# 3_Channel_Buck_Converter_Schematic.net
KiCad netlist of a schematic drawn in Altium Designer
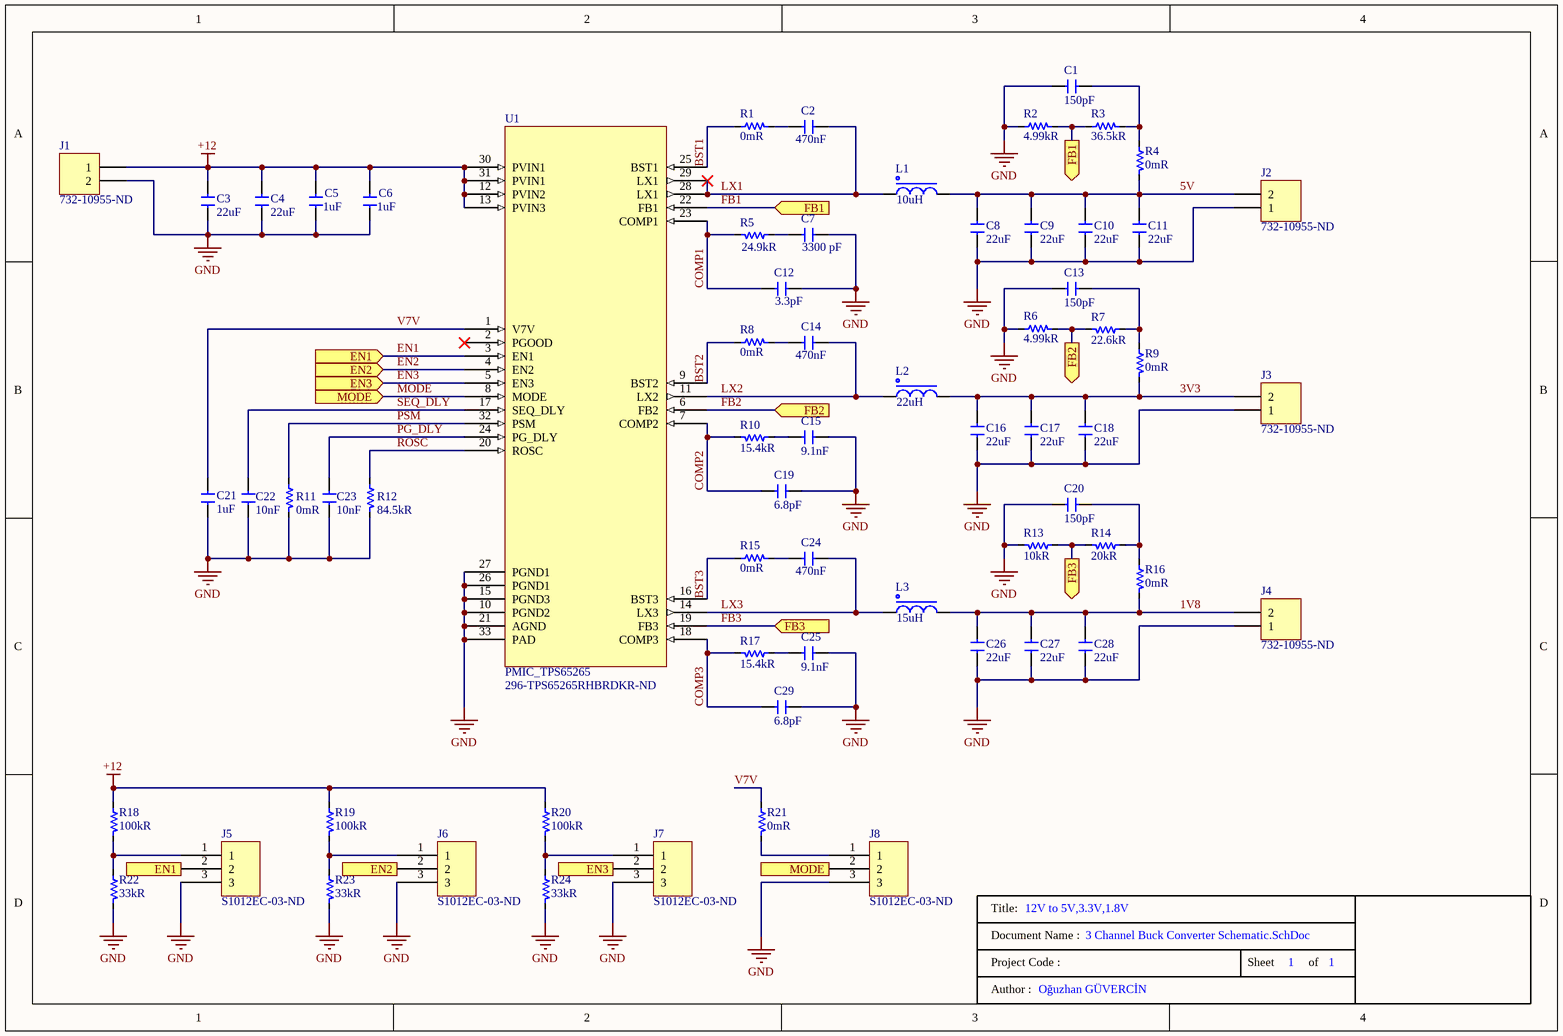
[diagram p0: 3 Channel Buck Converter Schematic.SchDoc]

(export (version "E")
  (design (tool "Eeschema 10.0.6"))
  (components
    (comp (ref "C1")
      (value "CAP_150pF_%1_0603_50V_NP0_CER")
      (footprint "0603_CAP")
      (description "0603 150 pF 50 V ±1 % Tolerance C0G/NP0 SMT Multilayer Ceramic Capacitor")
      (fields
        (field (name "MANUFACTURER") "Kyocera AVX")
        (field (name "MANUFACTURER PART NUMBER") "06035A151FAT2A")
        (field (name "CAPACITANCE") "150pF")
      )
      (libsource (lib "Main Schematic Library") (part "CAP_150pF_%1_0603_50V_NP0_CER"))
    )
    (comp (ref "C2")
      (value "CAP_0.47uF_%10_0603_25V_X7R_CER")
      (footprint "0603_CAP")
      (description "470nF Multilayer Ceramic Capacitor MLCC25 V; X7R Dielectric 0603 Surface Mount")
      (fields
        (field (name "MANUFACTURER") "Wurth Electronics")
        (field (name "MANUFACTURER PART NUMBER") "885012206075")
        (field (name "CAPACITANCE") "470nF")
      )
      (libsource (lib "Main Schematic Library") (part "CAP_0.47uF_%10_0603_25V_X7R_CER"))
    )
    (comp (ref "C3")
      (value "CAP_22uF_%10_1206_25V_X5R_CER")
      (footprint "1206_CAP")
      (description "1206 22 uF 25 V ±10% Tolerance X5R Multilayer Ceramic Chip Capacitor")
      (fields
        (field (name "MANUFACTURER") "Yageo")
        (field (name "MANUFACTURER PART NUMBER") "CC1206KKX5R8BB226")
        (field (name "CAPACITANCE") "22uF")
      )
      (libsource (lib "Main Schematic Library") (part "CAP_22uF_%10_1206_25V_X5R_CER"))
    )
    (comp (ref "C4")
      (value "CAP_22uF_%10_1206_25V_X5R_CER")
      (footprint "1206_CAP")
      (description "1206 22 uF 25 V ±10% Tolerance X5R Multilayer Ceramic Chip Capacitor")
      (fields
        (field (name "MANUFACTURER") "Yageo")
        (field (name "MANUFACTURER PART NUMBER") "CC1206KKX5R8BB226")
        (field (name "CAPACITANCE") "22uF")
      )
      (libsource (lib "Main Schematic Library") (part "CAP_22uF_%10_1206_25V_X5R_CER"))
    )
    (comp (ref "C5")
      (value "CAP_1uF_%10_0603_25V_X7R_CER")
      (footprint "0603_CAP")
      (description "TAPE DUCT CLOTH GRAY 3/4X 50YDS")
      (fields
        (field (name "MANUFACTURER") "Yageo")
        (field (name "MANUFACTURER PART NUMBER") "CC0603KPX7R8BB105")
        (field (name "CAPACITANCE") "1uF")
      )
      (libsource (lib "Main Schematic Library") (part "CAP_1uF_%10_0603_25V_X7R_CER"))
    )
    (comp (ref "C6")
      (value "CAP_1uF_%10_0603_25V_X7R_CER")
      (footprint "0603_CAP")
      (description "TAPE DUCT CLOTH GRAY 3/4X 50YDS")
      (fields
        (field (name "MANUFACTURER") "Yageo")
        (field (name "MANUFACTURER PART NUMBER") "CC0603KPX7R8BB105")
        (field (name "CAPACITANCE") "1uF")
      )
      (libsource (lib "Main Schematic Library") (part "CAP_1uF_%10_0603_25V_X7R_CER"))
    )
    (comp (ref "C7")
      (value "CAP_3300pF_0603_50V_X7R_CER")
      (footprint "0603_CAP")
      (description "3300 pF ±10% 50V Ceramic Capacitor X7R 0603 (1608 Metric)")
      (fields
        (field (name "MANUFACTURER") "Meritek")
        (field (name "MANUFACTURER PART NUMBER") "MA0603XR332K500")
        (field (name "CAPACITANCE") "3300 pF")
      )
      (libsource (lib "Main Schematic Library") (part "CAP_3300pF_0603_50V_X7R_CER"))
    )
    (comp (ref "C8")
      (value "CAP_22uF_%10_1206_25V_X5R_CER")
      (footprint "1206_CAP")
      (description "1206 22 uF 25 V ±10% Tolerance X5R Multilayer Ceramic Chip Capacitor")
      (fields
        (field (name "MANUFACTURER") "Yageo")
        (field (name "MANUFACTURER PART NUMBER") "CC1206KKX5R8BB226")
        (field (name "CAPACITANCE") "22uF")
      )
      (libsource (lib "Main Schematic Library") (part "CAP_22uF_%10_1206_25V_X5R_CER"))
    )
    (comp (ref "C9")
      (value "CAP_22uF_%10_1206_25V_X5R_CER")
      (footprint "1206_CAP")
      (description "1206 22 uF 25 V ±10% Tolerance X5R Multilayer Ceramic Chip Capacitor")
      (fields
        (field (name "MANUFACTURER") "Yageo")
        (field (name "MANUFACTURER PART NUMBER") "CC1206KKX5R8BB226")
        (field (name "CAPACITANCE") "22uF")
      )
      (libsource (lib "Main Schematic Library") (part "CAP_22uF_%10_1206_25V_X5R_CER"))
    )
    (comp (ref "C10")
      (value "CAP_22uF_%10_1206_25V_X5R_CER")
      (footprint "1206_CAP")
      (description "1206 22 uF 25 V ±10% Tolerance X5R Multilayer Ceramic Chip Capacitor")
      (fields
        (field (name "MANUFACTURER") "Yageo")
        (field (name "MANUFACTURER PART NUMBER") "CC1206KKX5R8BB226")
        (field (name "CAPACITANCE") "22uF")
      )
      (libsource (lib "Main Schematic Library") (part "CAP_22uF_%10_1206_25V_X5R_CER"))
    )
    (comp (ref "C11")
      (value "CAP_22uF_%10_1206_25V_X5R_CER")
      (footprint "1206_CAP")
      (description "1206 22 uF 25 V ±10% Tolerance X5R Multilayer Ceramic Chip Capacitor")
      (fields
        (field (name "MANUFACTURER") "Yageo")
        (field (name "MANUFACTURER PART NUMBER") "CC1206KKX5R8BB226")
        (field (name "CAPACITANCE") "22uF")
      )
      (libsource (lib "Main Schematic Library") (part "CAP_22uF_%10_1206_25V_X5R_CER"))
    )
    (comp (ref "C12")
      (value "CAP_3.3pF_±0.1pF_0603_50V_NP0_CER")
      (footprint "0603_CAP")
      (description "0603 3.3 pF 50 V ±0.1 pF Tolerance C0G/NP0 SMT Multilayer Ceramic Capacitor")
      (fields
        (field (name "MANUFACTURER") "Kyocera AVX")
        (field (name "MANUFACTURER PART NUMBER") "06035A3R3BAT2A")
        (field (name "CAPACITANCE") "3.3pF")
      )
      (libsource (lib "Main Schematic Library") (part "CAP_3.3pF_±0.1pF_0603_50V_NP0_CER"))
    )
    (comp (ref "C13")
      (value "CAP_150pF_%1_0603_50V_NP0_CER")
      (footprint "0603_CAP")
      (description "0603 150 pF 50 V ±1 % Tolerance C0G/NP0 SMT Multilayer Ceramic Capacitor")
      (fields
        (field (name "MANUFACTURER") "Kyocera AVX")
        (field (name "MANUFACTURER PART NUMBER") "06035A151FAT2A")
        (field (name "CAPACITANCE") "150pF")
      )
      (libsource (lib "Main Schematic Library") (part "CAP_150pF_%1_0603_50V_NP0_CER"))
    )
    (comp (ref "C14")
      (value "CAP_0.47uF_%10_0603_25V_X7R_CER")
      (footprint "0603_CAP")
      (description "470nF Multilayer Ceramic Capacitor MLCC25 V; X7R Dielectric 0603 Surface Mount")
      (fields
        (field (name "MANUFACTURER") "Wurth Electronics")
        (field (name "MANUFACTURER PART NUMBER") "885012206075")
        (field (name "CAPACITANCE") "470nF")
      )
      (libsource (lib "Main Schematic Library") (part "CAP_0.47uF_%10_0603_25V_X7R_CER"))
    )
    (comp (ref "C15")
      (value "CAP_9100pF_%5_0603_50V_U2J_CER")
      (footprint "0603_CAP")
      (description "Cap Ceramic 0.0091uF 50V U2J 5% Pad SMD 0603 Flexible Termination 125C T/R")
      (fields
        (field (name "MANUFACTURER") "KEMET")
        (field (name "MANUFACTURER PART NUMBER") "C0603X912J5JACTU")
        (field (name "CAPACITANCE") "9.1nF")
      )
      (libsource (lib "Main Schematic Library") (part "CAP_9100pF_%5_0603_50V_U2J_CER"))
    )
    (comp (ref "C16")
      (value "CAP_22uF_%10_1206_25V_X5R_CER")
      (footprint "1206_CAP")
      (description "1206 22 uF 25 V ±10% Tolerance X5R Multilayer Ceramic Chip Capacitor")
      (fields
        (field (name "MANUFACTURER") "Yageo")
        (field (name "MANUFACTURER PART NUMBER") "CC1206KKX5R8BB226")
        (field (name "CAPACITANCE") "22uF")
      )
      (libsource (lib "Main Schematic Library") (part "CAP_22uF_%10_1206_25V_X5R_CER"))
    )
    (comp (ref "C17")
      (value "CAP_22uF_%10_1206_25V_X5R_CER")
      (footprint "1206_CAP")
      (description "1206 22 uF 25 V ±10% Tolerance X5R Multilayer Ceramic Chip Capacitor")
      (fields
        (field (name "MANUFACTURER") "Yageo")
        (field (name "MANUFACTURER PART NUMBER") "CC1206KKX5R8BB226")
        (field (name "CAPACITANCE") "22uF")
      )
      (libsource (lib "Main Schematic Library") (part "CAP_22uF_%10_1206_25V_X5R_CER"))
    )
    (comp (ref "C18")
      (value "CAP_22uF_%10_1206_25V_X5R_CER")
      (footprint "1206_CAP")
      (description "1206 22 uF 25 V ±10% Tolerance X5R Multilayer Ceramic Chip Capacitor")
      (fields
        (field (name "MANUFACTURER") "Yageo")
        (field (name "MANUFACTURER PART NUMBER") "CC1206KKX5R8BB226")
        (field (name "CAPACITANCE") "22uF")
      )
      (libsource (lib "Main Schematic Library") (part "CAP_22uF_%10_1206_25V_X5R_CER"))
    )
    (comp (ref "C19")
      (value "CAP_6.8pF_±0.5p_0603_50V_C0G/NP0_CER")
      (footprint "0603_CAP")
      (description "0603 6.8 pF 50 V ±0.5 pF Tolerance C0G/NP0 SMT Multilayer Ceramic Capacitor")
      (fields
        (field (name "MANUFACTURER") "Kyocera AVX")
        (field (name "MANUFACTURER PART NUMBER") "06035A6R8DAT2A")
        (field (name "CAPACITANCE") "6.8pF")
      )
      (libsource (lib "Main Schematic Library") (part "CAP_6.8pF_±0.5p_0603_50V_C0G/NP0_CER"))
    )
    (comp (ref "C20")
      (value "CAP_150pF_%1_0603_50V_NP0_CER")
      (footprint "0603_CAP")
      (description "0603 150 pF 50 V ±1 % Tolerance C0G/NP0 SMT Multilayer Ceramic Capacitor")
      (fields
        (field (name "MANUFACTURER") "Kyocera AVX")
        (field (name "MANUFACTURER PART NUMBER") "06035A151FAT2A")
        (field (name "CAPACITANCE") "150pF")
      )
      (libsource (lib "Main Schematic Library") (part "CAP_150pF_%1_0603_50V_NP0_CER"))
    )
    (comp (ref "C21")
      (value "CAP_1uF_%10_0603_25V_X7R_CER")
      (footprint "0603_CAP")
      (description "TAPE DUCT CLOTH GRAY 3/4X 50YDS")
      (fields
        (field (name "MANUFACTURER") "Yageo")
        (field (name "MANUFACTURER PART NUMBER") "CC0603KPX7R8BB105")
        (field (name "CAPACITANCE") "1uF")
      )
      (libsource (lib "Main Schematic Library") (part "CAP_1uF_%10_0603_25V_X7R_CER"))
    )
    (comp (ref "C22")
      (value "CAP_10nF_%20_0603_50V_X7R_CER")
      (footprint "0603_CAP")
      (description "Cap Ceramic 0.01uF 50V X7R 20% SMD 0603 125°C Paper T/R")
      (fields
        (field (name "MANUFACTURER") "KEMET")
        (field (name "MANUFACTURER PART NUMBER") "C0603C103M5RAC7411")
        (field (name "CAPACITANCE") "10nF")
      )
      (libsource (lib "Main Schematic Library") (part "CAP_10nF_%20_0603_50V_X7R_CER"))
    )
    (comp (ref "C23")
      (value "CAP_10nF_%20_0603_50V_X7R_CER")
      (footprint "0603_CAP")
      (description "Cap Ceramic 0.01uF 50V X7R 20% SMD 0603 125°C Paper T/R")
      (fields
        (field (name "MANUFACTURER") "KEMET")
        (field (name "MANUFACTURER PART NUMBER") "C0603C103M5RAC7411")
        (field (name "CAPACITANCE") "10nF")
      )
      (libsource (lib "Main Schematic Library") (part "CAP_10nF_%20_0603_50V_X7R_CER"))
    )
    (comp (ref "C24")
      (value "CAP_0.47uF_%10_0603_25V_X7R_CER")
      (footprint "0603_CAP")
      (description "470nF Multilayer Ceramic Capacitor MLCC25 V; X7R Dielectric 0603 Surface Mount")
      (fields
        (field (name "MANUFACTURER") "Wurth Electronics")
        (field (name "MANUFACTURER PART NUMBER") "885012206075")
        (field (name "CAPACITANCE") "470nF")
      )
      (libsource (lib "Main Schematic Library") (part "CAP_0.47uF_%10_0603_25V_X7R_CER"))
    )
    (comp (ref "C25")
      (value "CAP_9100pF_%5_0603_50V_U2J_CER")
      (footprint "0603_CAP")
      (description "Cap Ceramic 0.0091uF 50V U2J 5% Pad SMD 0603 Flexible Termination 125C T/R")
      (fields
        (field (name "MANUFACTURER") "KEMET")
        (field (name "MANUFACTURER PART NUMBER") "C0603X912J5JACTU")
        (field (name "CAPACITANCE") "9.1nF")
      )
      (libsource (lib "Main Schematic Library") (part "CAP_9100pF_%5_0603_50V_U2J_CER"))
    )
    (comp (ref "C26")
      (value "CAP_22uF_%10_1206_25V_X5R_CER")
      (footprint "1206_CAP")
      (description "1206 22 uF 25 V ±10% Tolerance X5R Multilayer Ceramic Chip Capacitor")
      (fields
        (field (name "MANUFACTURER") "Yageo")
        (field (name "MANUFACTURER PART NUMBER") "CC1206KKX5R8BB226")
        (field (name "CAPACITANCE") "22uF")
      )
      (libsource (lib "Main Schematic Library") (part "CAP_22uF_%10_1206_25V_X5R_CER"))
    )
    (comp (ref "C27")
      (value "CAP_22uF_%10_1206_25V_X5R_CER")
      (footprint "1206_CAP")
      (description "1206 22 uF 25 V ±10% Tolerance X5R Multilayer Ceramic Chip Capacitor")
      (fields
        (field (name "MANUFACTURER") "Yageo")
        (field (name "MANUFACTURER PART NUMBER") "CC1206KKX5R8BB226")
        (field (name "CAPACITANCE") "22uF")
      )
      (libsource (lib "Main Schematic Library") (part "CAP_22uF_%10_1206_25V_X5R_CER"))
    )
    (comp (ref "C28")
      (value "CAP_22uF_%10_1206_25V_X5R_CER")
      (footprint "1206_CAP")
      (description "1206 22 uF 25 V ±10% Tolerance X5R Multilayer Ceramic Chip Capacitor")
      (fields
        (field (name "MANUFACTURER") "Yageo")
        (field (name "MANUFACTURER PART NUMBER") "CC1206KKX5R8BB226")
        (field (name "CAPACITANCE") "22uF")
      )
      (libsource (lib "Main Schematic Library") (part "CAP_22uF_%10_1206_25V_X5R_CER"))
    )
    (comp (ref "C29")
      (value "CAP_6.8pF_±0.5p_0603_50V_C0G/NP0_CER")
      (footprint "0603_CAP")
      (description "0603 6.8 pF 50 V ±0.5 pF Tolerance C0G/NP0 SMT Multilayer Ceramic Capacitor")
      (fields
        (field (name "MANUFACTURER") "Kyocera AVX")
        (field (name "MANUFACTURER PART NUMBER") "06035A6R8DAT2A")
        (field (name "CAPACITANCE") "6.8pF")
      )
      (libsource (lib "Main Schematic Library") (part "CAP_6.8pF_±0.5p_0603_50V_C0G/NP0_CER"))
    )
    (comp (ref "J1")
      (value "CON_1X2_Terminal Block")
      (footprint "1x2_TERMINAL BLOCK")
      (description "Series 1377 - 5.00 mm Horizontal Entry with Pressure Clamp WR-TBL, 2 pin")
      (fields
        (field (name "MANUFACTURER") "Wurth Electronics")
        (field (name "MANUFACTURER PART NUMBER") "691137710002")
        (field (name "SUPPLIER PART NUMBER 1") "732-10955-ND")
      )
      (libsource (lib "") (part "CON_1X2_Terminal Block_1"))
    )
    (comp (ref "J2")
      (value "CON_1X2_Terminal Block")
      (footprint "1x2_TERMINAL BLOCK")
      (description "Series 1377 - 5.00 mm Horizontal Entry with Pressure Clamp WR-TBL, 2 pin")
      (fields
        (field (name "MANUFACTURER") "Wurth Electronics")
        (field (name "MANUFACTURER PART NUMBER") "691137710002")
        (field (name "SUPPLIER PART NUMBER 1") "732-10955-ND")
      )
      (libsource (lib "Main Schematic Library") (part "CON_1X2_Terminal Block"))
    )
    (comp (ref "J3")
      (value "CON_1X2_Terminal Block")
      (footprint "1x2_TERMINAL BLOCK")
      (description "Series 1377 - 5.00 mm Horizontal Entry with Pressure Clamp WR-TBL, 2 pin")
      (fields
        (field (name "MANUFACTURER") "Wurth Electronics")
        (field (name "MANUFACTURER PART NUMBER") "691137710002")
        (field (name "SUPPLIER PART NUMBER 1") "732-10955-ND")
      )
      (libsource (lib "Main Schematic Library") (part "CON_1X2_Terminal Block"))
    )
    (comp (ref "J4")
      (value "CON_1X2_Terminal Block")
      (footprint "1x2_TERMINAL BLOCK")
      (description "Series 1377 - 5.00 mm Horizontal Entry with Pressure Clamp WR-TBL, 2 pin")
      (fields
        (field (name "MANUFACTURER") "Wurth Electronics")
        (field (name "MANUFACTURER PART NUMBER") "691137710002")
        (field (name "SUPPLIER PART NUMBER 1") "732-10955-ND")
      )
      (libsource (lib "Main Schematic Library") (part "CON_1X2_Terminal Block"))
    )
    (comp (ref "J5")
      (value "CON_1X3_2.54mm_Male Header")
      (footprint "DIP_1X3_HEADER_2.54_PITCH")
      (description "Conn Header Vert 3POS 2.54MM")
      (fields
        (field (name "MANUFACTURER") "Sullins")
        (field (name "MANUFACTURER PART NUMBER") "PREC003SAAN-RC")
        (field (name "SUPPLIER PART NUMBER 1") "S1012EC-03-ND")
      )
      (libsource (lib "Main Schematic Library") (part "CON_1X3_2.54mm_Male Header"))
    )
    (comp (ref "J6")
      (value "CON_1X3_2.54mm_Male Header")
      (footprint "DIP_1X3_HEADER_2.54_PITCH")
      (description "Conn Header Vert 3POS 2.54MM")
      (fields
        (field (name "MANUFACTURER") "Sullins")
        (field (name "MANUFACTURER PART NUMBER") "PREC003SAAN-RC")
        (field (name "SUPPLIER PART NUMBER 1") "S1012EC-03-ND")
      )
      (libsource (lib "Main Schematic Library") (part "CON_1X3_2.54mm_Male Header"))
    )
    (comp (ref "J7")
      (value "CON_1X3_2.54mm_Male Header")
      (footprint "DIP_1X3_HEADER_2.54_PITCH")
      (description "Conn Header Vert 3POS 2.54MM")
      (fields
        (field (name "MANUFACTURER") "Sullins")
        (field (name "MANUFACTURER PART NUMBER") "PREC003SAAN-RC")
        (field (name "SUPPLIER PART NUMBER 1") "S1012EC-03-ND")
      )
      (libsource (lib "Main Schematic Library") (part "CON_1X3_2.54mm_Male Header"))
    )
    (comp (ref "J8")
      (value "CON_1X3_2.54mm_Male Header")
      (footprint "DIP_1X3_HEADER_2.54_PITCH")
      (description "Conn Header Vert 3POS 2.54MM")
      (fields
        (field (name "MANUFACTURER") "Sullins")
        (field (name "MANUFACTURER PART NUMBER") "PREC003SAAN-RC")
        (field (name "SUPPLIER PART NUMBER 1") "S1012EC-03-ND")
      )
      (libsource (lib "Main Schematic Library") (part "CON_1X3_2.54mm_Male Header"))
    )
    (comp (ref "L1")
      (value "IND_10uH_5A_26.5 mOHM_SMD")
      (footprint "INDP120120X100N")
      (description "Fixed Ind 10UH 5A 26.5 Mohm SMD")
      (fields
        (field (name "MANUFACTURER") "Wurth Electronics")
        (field (name "MANUFACTURER PART NUMBER") "784771100")
        (field (name "INDUCTANCE") "10uH")
      )
      (libsource (lib "Main Schematic Library") (part "IND_10uH_5A_26.5 mOHM_SMD"))
    )
    (comp (ref "L2")
      (value "IND_22uH_3.2A_40 mOHM_SMD")
      (footprint "INDP120120X100N")
      (description "Fixed Ind 22UH 3.2A 40 Mohm SMD")
      (fields
        (field (name "MANUFACTURER") "Wurth Electronics")
        (field (name "MANUFACTURER PART NUMBER") "784771220")
        (field (name "INDUCTANCE") "22uH")
      )
      (libsource (lib "Main Schematic Library") (part "IND_22uH_3.2A_40 mOHM_SMD"))
    )
    (comp (ref "L3")
      (value "IND_15uH_4.6A_36 mOHM_SMD")
      (footprint "INDP120120X100N")
      (description "Inductor, Aec-Q200, 15Uh, Shld, 4.6A Rohs Compliant: Yes")
      (fields
        (field (name "MANUFACTURER") "Wurth Electronics")
        (field (name "MANUFACTURER PART NUMBER") "7847709150")
        (field (name "INDUCTANCE") "15uH")
      )
      (libsource (lib "Main Schematic Library") (part "IND_15uH_4.6A_36 mOHM_SMD"))
    )
    (comp (ref "R1")
      (value "RES_0 OHM_JUMPER_0603_1/10W")
      (footprint "0603_RES")
      (description "CRCW Thick Film Commodity Chip Resistor Jumper 0603 Size 0 Ohm 0.1 W 2-Pin SMD Paper T/R")
      (fields
        (field (name "MANUFACTURER") "Vishay")
        (field (name "MANUFACTURER PART NUMBER") "CRCW06030000Z0EBC")
        (field (name "RESISTANCE") "0mR")
      )
      (libsource (lib "Main Schematic Library") (part "RES_0 OHM_JUMPER_0603_1/10W"))
    )
    (comp (ref "R2")
      (value "RES_4.99K OHM_1%_0603_1/10W")
      (footprint "0603_RES")
      (description "Res Thick Film 0603 4.99K Ohm 1% 1/10W ±100ppm/°C Molded SMD SMD Paper T/R")
      (fields
        (field (name "MANUFACTURER") "Vishay Dale")
        (field (name "MANUFACTURER PART NUMBER") "CRCW06034K99FKEB")
        (field (name "RESISTANCE") "4.99kR")
      )
      (libsource (lib "Main Schematic Library") (part "RES_4.99K OHM_1%_0603_1/10W"))
    )
    (comp (ref "R3")
      (value "RES_36.5K OHM_1%_0603_1/10W")
      (footprint "0603_RES")
      (description "Res Thick Film 0603 36.5K Ohm 1% 0.1W(1/10W) ±100ppm/C Molded SMD Automotive Paper T/R")
      (fields
        (field (name "MANUFACTURER") "Vishay")
        (field (name "MANUFACTURER PART NUMBER") "CRCW060336K5FKEA")
        (field (name "RESISTANCE") "36.5kR")
      )
      (libsource (lib "Main Schematic Library") (part "RES_36.5K OHM_1%_0603_1/10W"))
    )
    (comp (ref "R4")
      (value "RES_0 OHM_JUMPER_0603_1/10W")
      (footprint "0603_RES")
      (description "CRCW Thick Film Commodity Chip Resistor Jumper 0603 Size 0 Ohm 0.1 W 2-Pin SMD Paper T/R")
      (fields
        (field (name "MANUFACTURER") "Vishay")
        (field (name "MANUFACTURER PART NUMBER") "CRCW06030000Z0EBC")
        (field (name "RESISTANCE") "0mR")
      )
      (libsource (lib "Main Schematic Library") (part "RES_0 OHM_JUMPER_0603_1/10W"))
    )
    (comp (ref "R5")
      (value "RES_24.9K OHM_1%_0603_1/10W")
      (footprint "0603_RES")
      (description "Res Thick Film 0603 24.9K Ohm 1% 1/10W ±100ppm/°C Molded SMD SMD Paper T/R")
      (fields
        (field (name "MANUFACTURER") "Vishay Dale")
        (field (name "MANUFACTURER PART NUMBER") "CRCW060324K9FKTA")
        (field (name "RESISTANCE") "24.9kR")
      )
      (libsource (lib "Main Schematic Library") (part "RES_24.9K OHM_1%_0603_1/10W"))
    )
    (comp (ref "R6")
      (value "RES_4.99K OHM_1%_0603_1/10W")
      (footprint "0603_RES")
      (description "Res Thick Film 0603 4.99K Ohm 1% 1/10W ±100ppm/°C Molded SMD SMD Paper T/R")
      (fields
        (field (name "MANUFACTURER") "Vishay Dale")
        (field (name "MANUFACTURER PART NUMBER") "CRCW06034K99FKEB")
        (field (name "RESISTANCE") "4.99kR")
      )
      (libsource (lib "Main Schematic Library") (part "RES_4.99K OHM_1%_0603_1/10W"))
    )
    (comp (ref "R7")
      (value "RES_22.6K OHM_1%_0603_1/10W")
      (footprint "0603_RES")
      (description "CRCW Thick Film Commodity Chip Resistor 0603 Size 22.6K Ohm 1% 0.1 W 100 ppm/K 2-Pin SMD Paper T/R")
      (fields
        (field (name "MANUFACTURER") "Vishay")
        (field (name "MANUFACTURER PART NUMBER") "CRCW060322K6FKEBC")
        (field (name "RESISTANCE") "22.6kR")
      )
      (libsource (lib "Main Schematic Library") (part "RES_22.6K OHM_1%_0603_1/10W"))
    )
    (comp (ref "R8")
      (value "RES_0 OHM_JUMPER_0603_1/10W")
      (footprint "0603_RES")
      (description "CRCW Thick Film Commodity Chip Resistor Jumper 0603 Size 0 Ohm 0.1 W 2-Pin SMD Paper T/R")
      (fields
        (field (name "MANUFACTURER") "Vishay")
        (field (name "MANUFACTURER PART NUMBER") "CRCW06030000Z0EBC")
        (field (name "RESISTANCE") "0mR")
      )
      (libsource (lib "Main Schematic Library") (part "RES_0 OHM_JUMPER_0603_1/10W"))
    )
    (comp (ref "R9")
      (value "RES_0 OHM_JUMPER_0603_1/10W")
      (footprint "0603_RES")
      (description "CRCW Thick Film Commodity Chip Resistor Jumper 0603 Size 0 Ohm 0.1 W 2-Pin SMD Paper T/R")
      (fields
        (field (name "MANUFACTURER") "Vishay")
        (field (name "MANUFACTURER PART NUMBER") "CRCW06030000Z0EBC")
        (field (name "RESISTANCE") "0mR")
      )
      (libsource (lib "Main Schematic Library") (part "RES_0 OHM_JUMPER_0603_1/10W"))
    )
    (comp (ref "R10")
      (value "RES_15.4K OHM_1%_0603_1/10W")
      (footprint "0603_RES")
      (description "Res SMD 15.4K Ohm 1% 1/10W 0603")
      (fields
        (field (name "MANUFACTURER") "Vishay Dale")
        (field (name "MANUFACTURER PART NUMBER") "CRCW060315K4FKEB")
        (field (name "RESISTANCE") "15.4kR")
      )
      (libsource (lib "Main Schematic Library") (part "RES_15.4K OHM_1%_0603_1/10W"))
    )
    (comp (ref "R11")
      (value "RES_0 OHM_JUMPER_0603_1/10W")
      (footprint "0603_RES")
      (description "CRCW Thick Film Commodity Chip Resistor Jumper 0603 Size 0 Ohm 0.1 W 2-Pin SMD Paper T/R")
      (fields
        (field (name "MANUFACTURER") "Vishay")
        (field (name "MANUFACTURER PART NUMBER") "CRCW06030000Z0EBC")
        (field (name "RESISTANCE") "0mR")
      )
      (libsource (lib "Main Schematic Library") (part "RES_0 OHM_JUMPER_0603_1/10W"))
    )
    (comp (ref "R12")
      (value "RES_84.5K OHM_1%_0603_1/10W")
      (footprint "0603_RES")
      (description "Res Thick Film 0603 84.5K Ohm 1% 1/10W ±100ppm/°C Molded SMD SMD Paper T/R")
      (fields
        (field (name "MANUFACTURER") "Vishay")
        (field (name "MANUFACTURER PART NUMBER") "CRCW060384K5FKEA")
        (field (name "RESISTANCE") "84.5kR")
      )
      (libsource (lib "Main Schematic Library") (part "RES_84.5K OHM_1%_0603_1/10W"))
    )
    (comp (ref "R13")
      (value "RES_10K OHM_1%_0603_1/10W")
      (footprint "0603_RES")
      (description "Res Thick Film 0603 10K Ohm 1% 0.1W(1/10W) ±100ppm/C Pad SMD Automotive T/R")
      (fields
        (field (name "MANUFACTURER") "Vishay Dale")
        (field (name "MANUFACTURER PART NUMBER") "CRCW060310K0FKEE")
        (field (name "RESISTANCE") "10kR")
      )
      (libsource (lib "Main Schematic Library") (part "RES_10K OHM_1%_0603_1/10W"))
    )
    (comp (ref "R14")
      (value "RES_20K OHM _1%_0603_1/10W")
      (footprint "0603_RES")
      (description "Res Thick Film 0603 20K Ohm 1% 1/10W ±100ppm/°C Molded SMD SMD Paper T/R")
      (fields
        (field (name "MANUFACTURER") "Vishay Dale")
        (field (name "MANUFACTURER PART NUMBER") "CRCW060320K0FKEB")
        (field (name "RESISTANCE") "20kR")
      )
      (libsource (lib "Main Schematic Library") (part "RES_20K OHM _1%_0603_1/10W"))
    )
    (comp (ref "R15")
      (value "RES_0 OHM_JUMPER_0603_1/10W")
      (footprint "0603_RES")
      (description "CRCW Thick Film Commodity Chip Resistor Jumper 0603 Size 0 Ohm 0.1 W 2-Pin SMD Paper T/R")
      (fields
        (field (name "MANUFACTURER") "Vishay")
        (field (name "MANUFACTURER PART NUMBER") "CRCW06030000Z0EBC")
        (field (name "RESISTANCE") "0mR")
      )
      (libsource (lib "Main Schematic Library") (part "RES_0 OHM_JUMPER_0603_1/10W"))
    )
    (comp (ref "R16")
      (value "RES_0 OHM_JUMPER_0603_1/10W")
      (footprint "0603_RES")
      (description "CRCW Thick Film Commodity Chip Resistor Jumper 0603 Size 0 Ohm 0.1 W 2-Pin SMD Paper T/R")
      (fields
        (field (name "MANUFACTURER") "Vishay")
        (field (name "MANUFACTURER PART NUMBER") "CRCW06030000Z0EBC")
        (field (name "RESISTANCE") "0mR")
      )
      (libsource (lib "Main Schematic Library") (part "RES_0 OHM_JUMPER_0603_1/10W"))
    )
    (comp (ref "R17")
      (value "RES_15.4K OHM_1%_0603_1/10W")
      (footprint "0603_RES")
      (description "Res SMD 15.4K Ohm 1% 1/10W 0603")
      (fields
        (field (name "MANUFACTURER") "Vishay Dale")
        (field (name "MANUFACTURER PART NUMBER") "CRCW060315K4FKEB")
        (field (name "RESISTANCE") "15.4kR")
      )
      (libsource (lib "Main Schematic Library") (part "RES_15.4K OHM_1%_0603_1/10W"))
    )
    (comp (ref "R18")
      (value "RES_100K OHM_5%_0603_1/10W")
      (footprint "0603_RES")
      (description "Res Thick Film 0603 100K Ohm 5% 1/10W ±200ppm/°C Molded SMD SMD Paper T/R")
      (fields
        (field (name "MANUFACTURER") "Vishay Dale")
        (field (name "MANUFACTURER PART NUMBER") "CRCW0603100KJNEB")
        (field (name "RESISTANCE") "100kR")
      )
      (libsource (lib "Main Schematic Library") (part "RES_100K OHM_5%_0603_1/10W"))
    )
    (comp (ref "R19")
      (value "RES_100K OHM_5%_0603_1/10W")
      (footprint "0603_RES")
      (description "Res Thick Film 0603 100K Ohm 5% 1/10W ±200ppm/°C Molded SMD SMD Paper T/R")
      (fields
        (field (name "MANUFACTURER") "Vishay Dale")
        (field (name "MANUFACTURER PART NUMBER") "CRCW0603100KJNEB")
        (field (name "RESISTANCE") "100kR")
      )
      (libsource (lib "Main Schematic Library") (part "RES_100K OHM_5%_0603_1/10W"))
    )
    (comp (ref "R20")
      (value "RES_100K OHM_5%_0603_1/10W")
      (footprint "0603_RES")
      (description "Res Thick Film 0603 100K Ohm 5% 1/10W ±200ppm/°C Molded SMD SMD Paper T/R")
      (fields
        (field (name "MANUFACTURER") "Vishay Dale")
        (field (name "MANUFACTURER PART NUMBER") "CRCW0603100KJNEB")
        (field (name "RESISTANCE") "100kR")
      )
      (libsource (lib "Main Schematic Library") (part "RES_100K OHM_5%_0603_1/10W"))
    )
    (comp (ref "R21")
      (value "RES_0 OHM_JUMPER_0603_1/10W")
      (footprint "0603_RES")
      (description "CRCW Thick Film Commodity Chip Resistor Jumper 0603 Size 0 Ohm 0.1 W 2-Pin SMD Paper T/R")
      (fields
        (field (name "MANUFACTURER") "Vishay")
        (field (name "MANUFACTURER PART NUMBER") "CRCW06030000Z0EBC")
        (field (name "RESISTANCE") "0mR")
      )
      (libsource (lib "Main Schematic Library") (part "RES_0 OHM_JUMPER_0603_1/10W"))
    )
    (comp (ref "R22")
      (value "RES_33K OHM_5%_0603_1/10W")
      (footprint "0603_RES")
      (description "Res Thick Film 0603 33K Ohm 5% 1/10W ±200ppm/°C Molded SMD SMD Paper T/R")
      (fields
        (field (name "MANUFACTURER") "Vishay Dale")
        (field (name "MANUFACTURER PART NUMBER") "CRCW060333K0JNEA")
        (field (name "RESISTANCE") "33kR")
      )
      (libsource (lib "Main Schematic Library") (part "RES_33K OHM_5%_0603_1/10W"))
    )
    (comp (ref "R23")
      (value "RES_33K OHM_5%_0603_1/10W")
      (footprint "0603_RES")
      (description "Res Thick Film 0603 33K Ohm 5% 1/10W ±200ppm/°C Molded SMD SMD Paper T/R")
      (fields
        (field (name "MANUFACTURER") "Vishay Dale")
        (field (name "MANUFACTURER PART NUMBER") "CRCW060333K0JNEA")
        (field (name "RESISTANCE") "33kR")
      )
      (libsource (lib "Main Schematic Library") (part "RES_33K OHM_5%_0603_1/10W"))
    )
    (comp (ref "R24")
      (value "RES_33K OHM_5%_0603_1/10W")
      (footprint "0603_RES")
      (description "Res Thick Film 0603 33K Ohm 5% 1/10W ±200ppm/°C Molded SMD SMD Paper T/R")
      (fields
        (field (name "MANUFACTURER") "Vishay Dale")
        (field (name "MANUFACTURER PART NUMBER") "CRCW060333K0JNEA")
        (field (name "RESISTANCE") "33kR")
      )
      (libsource (lib "Main Schematic Library") (part "RES_33K OHM_5%_0603_1/10W"))
    )
    (comp (ref "U1")
      (value "PMIC_TPS65265")
      (footprint "QFN50P500X500X100_HS-33N")
      (description "4.5- to 17-V Input Voltage, 5-A/3-A/2-A Output Current Triple Buck Converter 32-VQFN -40 to 85")
      (fields
        (field (name "MANUFACTURER") "Texas Instruments")
        (field (name "MANUFACTURER PART NUMBER") "TPS65265RHBR")
        (field (name "SUPPLIER PART NUMBER 1") "296-TPS65265RHBRDKR-ND")
      )
      (libsource (lib "Main Schematic Library") (part "PMIC_TPS65265"))
    )
  )
  (nets
    (net (code "1") (name "+12") (class "Default")
      (node (ref "C3") (pin "2") (pinfunction "2_2") (pintype "passive"))
      (node (ref "C4") (pin "2") (pinfunction "2_2") (pintype "passive"))
      (node (ref "C5") (pin "2") (pinfunction "2_2") (pintype "passive"))
      (node (ref "C6") (pin "2") (pinfunction "2_2") (pintype "passive"))
      (node (ref "J1") (pin "1") (pinfunction "1_1") (pintype "passive"))
      (node (ref "R18") (pin "2") (pinfunction "2_2") (pintype "passive"))
      (node (ref "R19") (pin "2") (pinfunction "2_2") (pintype "passive"))
      (node (ref "R20") (pin "2") (pinfunction "2_2") (pintype "passive"))
      (node (ref "U1") (pin "12") (pinfunction "PVIN2_12") (pintype "input"))
      (node (ref "U1") (pin "13") (pinfunction "PVIN3_13") (pintype "input"))
      (node (ref "U1") (pin "30") (pinfunction "PVIN1_30") (pintype "input"))
      (node (ref "U1") (pin "31") (pinfunction "PVIN1_31") (pintype "input"))
    )
    (net (code "2") (name "/1V8") (class "Default")
      (node (ref "C26") (pin "2") (pinfunction "2_2") (pintype "passive"))
      (node (ref "C27") (pin "2") (pinfunction "2_2") (pintype "passive"))
      (node (ref "C28") (pin "2") (pinfunction "2_2") (pintype "passive"))
      (node (ref "J4") (pin "2") (pinfunction "2_2") (pintype "passive"))
      (node (ref "L3") (pin "2") (pinfunction "2_2") (pintype "passive"))
      (node (ref "R16") (pin "2") (pinfunction "2_2") (pintype "passive"))
    )
    (net (code "3") (name "/3V3") (class "Default")
      (node (ref "C16") (pin "2") (pinfunction "2_2") (pintype "passive"))
      (node (ref "C17") (pin "2") (pinfunction "2_2") (pintype "passive"))
      (node (ref "C18") (pin "2") (pinfunction "2_2") (pintype "passive"))
      (node (ref "J3") (pin "2") (pinfunction "2_2") (pintype "passive"))
      (node (ref "L2") (pin "2") (pinfunction "2_2") (pintype "passive"))
      (node (ref "R9") (pin "2") (pinfunction "2_2") (pintype "passive"))
    )
    (net (code "4") (name "/5V") (class "Default")
      (node (ref "C10") (pin "2") (pinfunction "2_2") (pintype "passive"))
      (node (ref "C11") (pin "2") (pinfunction "2_2") (pintype "passive"))
      (node (ref "C8") (pin "2") (pinfunction "2_2") (pintype "passive"))
      (node (ref "C9") (pin "2") (pinfunction "2_2") (pintype "passive"))
      (node (ref "J2") (pin "2") (pinfunction "2_2") (pintype "passive"))
      (node (ref "L1") (pin "2") (pinfunction "2_2") (pintype "passive"))
      (node (ref "R4") (pin "2") (pinfunction "2_2") (pintype "passive"))
    )
    (net (code "5") (name "/BST1") (class "Default")
      (node (ref "R1") (pin "2") (pinfunction "2_2") (pintype "passive"))
      (node (ref "U1") (pin "25") (pinfunction "BST1_25") (pintype "input"))
    )
    (net (code "6") (name "/BST2") (class "Default")
      (node (ref "R8") (pin "2") (pinfunction "2_2") (pintype "passive"))
      (node (ref "U1") (pin "9") (pinfunction "BST2_9") (pintype "input"))
    )
    (net (code "7") (name "/BST3") (class "Default")
      (node (ref "R15") (pin "2") (pinfunction "2_2") (pintype "passive"))
      (node (ref "U1") (pin "16") (pinfunction "BST3_16") (pintype "input"))
    )
    (net (code "8") (name "/COMP1") (class "Default")
      (node (ref "C12") (pin "1") (pinfunction "1_1") (pintype "passive"))
      (node (ref "R5") (pin "1") (pinfunction "1_1") (pintype "passive"))
      (node (ref "U1") (pin "23") (pinfunction "COMP1_23") (pintype "input"))
    )
    (net (code "9") (name "/COMP2") (class "Default")
      (node (ref "C19") (pin "1") (pinfunction "1_1") (pintype "passive"))
      (node (ref "R10") (pin "1") (pinfunction "1_1") (pintype "passive"))
      (node (ref "U1") (pin "7") (pinfunction "COMP2_7") (pintype "input"))
    )
    (net (code "10") (name "/COMP3") (class "Default")
      (node (ref "C29") (pin "1") (pinfunction "1_1") (pintype "passive"))
      (node (ref "R17") (pin "1") (pinfunction "1_1") (pintype "passive"))
      (node (ref "U1") (pin "18") (pinfunction "COMP3_18") (pintype "input"))
    )
    (net (code "11") (name "/EN1") (class "Default")
      (node (ref "J5") (pin "2") (pinfunction "2_2") (pintype "passive"))
      (node (ref "U1") (pin "3") (pinfunction "EN1_3") (pintype "input"))
    )
    (net (code "12") (name "/EN2") (class "Default")
      (node (ref "J6") (pin "2") (pinfunction "2_2") (pintype "passive"))
      (node (ref "U1") (pin "4") (pinfunction "EN2_4") (pintype "input"))
    )
    (net (code "13") (name "/EN3") (class "Default")
      (node (ref "J7") (pin "2") (pinfunction "2_2") (pintype "passive"))
      (node (ref "U1") (pin "5") (pinfunction "EN3_5") (pintype "input"))
    )
    (net (code "14") (name "/FB1") (class "Default")
      (node (ref "R2") (pin "2") (pinfunction "2_2") (pintype "passive"))
      (node (ref "R3") (pin "1") (pinfunction "1_1") (pintype "passive"))
      (node (ref "U1") (pin "22") (pinfunction "FB1_22") (pintype "input"))
    )
    (net (code "15") (name "/FB2") (class "Default")
      (node (ref "R6") (pin "2") (pinfunction "2_2") (pintype "passive"))
      (node (ref "R7") (pin "1") (pinfunction "1_1") (pintype "passive"))
      (node (ref "U1") (pin "6") (pinfunction "FB2_6") (pintype "input"))
    )
    (net (code "16") (name "/FB3") (class "Default")
      (node (ref "R13") (pin "2") (pinfunction "2_2") (pintype "passive"))
      (node (ref "R14") (pin "1") (pinfunction "1_1") (pintype "passive"))
      (node (ref "U1") (pin "19") (pinfunction "FB3_19") (pintype "input"))
    )
    (net (code "17") (name "/LX1") (class "Default")
      (node (ref "C2") (pin "2") (pinfunction "2_2") (pintype "passive"))
      (node (ref "L1") (pin "1") (pinfunction "1_1") (pintype "passive"))
      (node (ref "U1") (pin "28") (pinfunction "LX1_28") (pintype "output"))
      (node (ref "U1") (pin "29") (pinfunction "LX1_29") (pintype "output"))
    )
    (net (code "18") (name "/LX2") (class "Default")
      (node (ref "C14") (pin "2") (pinfunction "2_2") (pintype "passive"))
      (node (ref "L2") (pin "1") (pinfunction "1_1") (pintype "passive"))
      (node (ref "U1") (pin "11") (pinfunction "LX2_11") (pintype "output"))
    )
    (net (code "19") (name "/LX3") (class "Default")
      (node (ref "C24") (pin "2") (pinfunction "2_2") (pintype "passive"))
      (node (ref "L3") (pin "1") (pinfunction "1_1") (pintype "passive"))
      (node (ref "U1") (pin "14") (pinfunction "LX3_14") (pintype "output"))
    )
    (net (code "20") (name "/MODE") (class "Default")
      (node (ref "J8") (pin "2") (pinfunction "2_2") (pintype "passive"))
      (node (ref "U1") (pin "8") (pinfunction "MODE_8") (pintype "input"))
    )
    (net (code "21") (name "/PG_DLY") (class "Default")
      (node (ref "C23") (pin "2") (pinfunction "2_2") (pintype "passive"))
      (node (ref "U1") (pin "24") (pinfunction "PG_DLY_24") (pintype "input"))
    )
    (net (code "22") (name "/PSM") (class "Default")
      (node (ref "R11") (pin "2") (pinfunction "2_2") (pintype "passive"))
      (node (ref "U1") (pin "32") (pinfunction "PSM_32") (pintype "input"))
    )
    (net (code "23") (name "/ROSC") (class "Default")
      (node (ref "R12") (pin "2") (pinfunction "2_2") (pintype "passive"))
      (node (ref "U1") (pin "20") (pinfunction "ROSC_20") (pintype "input"))
    )
    (net (code "24") (name "/SEQ_DLY") (class "Default")
      (node (ref "C22") (pin "2") (pinfunction "2_2") (pintype "passive"))
      (node (ref "U1") (pin "17") (pinfunction "SEQ_DLY_17") (pintype "input"))
    )
    (net (code "25") (name "/V7V") (class "Default")
      (node (ref "C21") (pin "1") (pinfunction "1_1") (pintype "passive"))
      (node (ref "R21") (pin "2") (pinfunction "2_2") (pintype "passive"))
      (node (ref "U1") (pin "1") (pinfunction "V7V_1") (pintype "input"))
    )
    (net (code "26") (name "GND") (class "Default")
      (node (ref "C1") (pin "1") (pinfunction "1_1") (pintype "passive"))
      (node (ref "C10") (pin "1") (pinfunction "1_1") (pintype "passive"))
      (node (ref "C11") (pin "1") (pinfunction "1_1") (pintype "passive"))
      (node (ref "C12") (pin "2") (pinfunction "2_2") (pintype "passive"))
      (node (ref "C13") (pin "1") (pinfunction "1_1") (pintype "passive"))
      (node (ref "C15") (pin "2") (pinfunction "2_2") (pintype "passive"))
      (node (ref "C16") (pin "1") (pinfunction "1_1") (pintype "passive"))
      (node (ref "C17") (pin "1") (pinfunction "1_1") (pintype "passive"))
      (node (ref "C18") (pin "1") (pinfunction "1_1") (pintype "passive"))
      (node (ref "C19") (pin "2") (pinfunction "2_2") (pintype "passive"))
      (node (ref "C20") (pin "1") (pinfunction "1_1") (pintype "passive"))
      (node (ref "C21") (pin "2") (pinfunction "2_2") (pintype "passive"))
      (node (ref "C22") (pin "1") (pinfunction "1_1") (pintype "passive"))
      (node (ref "C23") (pin "1") (pinfunction "1_1") (pintype "passive"))
      (node (ref "C25") (pin "2") (pinfunction "2_2") (pintype "passive"))
      (node (ref "C26") (pin "1") (pinfunction "1_1") (pintype "passive"))
      (node (ref "C27") (pin "1") (pinfunction "1_1") (pintype "passive"))
      (node (ref "C28") (pin "1") (pinfunction "1_1") (pintype "passive"))
      (node (ref "C29") (pin "2") (pinfunction "2_2") (pintype "passive"))
      (node (ref "C3") (pin "1") (pinfunction "1_1") (pintype "passive"))
      (node (ref "C4") (pin "1") (pinfunction "1_1") (pintype "passive"))
      (node (ref "C5") (pin "1") (pinfunction "1_1") (pintype "passive"))
      (node (ref "C6") (pin "1") (pinfunction "1_1") (pintype "passive"))
      (node (ref "C7") (pin "2") (pinfunction "2_2") (pintype "passive"))
      (node (ref "C8") (pin "1") (pinfunction "1_1") (pintype "passive"))
      (node (ref "C9") (pin "1") (pinfunction "1_1") (pintype "passive"))
      (node (ref "J1") (pin "2") (pinfunction "2_2") (pintype "passive"))
      (node (ref "J2") (pin "1") (pinfunction "1_1") (pintype "passive"))
      (node (ref "J3") (pin "1") (pinfunction "1_1") (pintype "passive"))
      (node (ref "J4") (pin "1") (pinfunction "1_1") (pintype "passive"))
      (node (ref "J5") (pin "3") (pinfunction "3_3") (pintype "passive"))
      (node (ref "J6") (pin "3") (pinfunction "3_3") (pintype "passive"))
      (node (ref "J7") (pin "3") (pinfunction "3_3") (pintype "passive"))
      (node (ref "J8") (pin "3") (pinfunction "3_3") (pintype "passive"))
      (node (ref "R11") (pin "1") (pinfunction "1_1") (pintype "passive"))
      (node (ref "R12") (pin "1") (pinfunction "1_1") (pintype "passive"))
      (node (ref "R13") (pin "1") (pinfunction "1_1") (pintype "passive"))
      (node (ref "R2") (pin "1") (pinfunction "1_1") (pintype "passive"))
      (node (ref "R22") (pin "1") (pinfunction "1_1") (pintype "passive"))
      (node (ref "R23") (pin "1") (pinfunction "1_1") (pintype "passive"))
      (node (ref "R24") (pin "1") (pinfunction "1_1") (pintype "passive"))
      (node (ref "R6") (pin "1") (pinfunction "1_1") (pintype "passive"))
      (node (ref "U1") (pin "10") (pinfunction "PGND2_10") (pintype "passive"))
      (node (ref "U1") (pin "15") (pinfunction "PGND3_15") (pintype "passive"))
      (node (ref "U1") (pin "21") (pinfunction "AGND_21") (pintype "passive"))
      (node (ref "U1") (pin "26") (pinfunction "PGND1_26") (pintype "passive"))
      (node (ref "U1") (pin "27") (pinfunction "PGND1_27") (pintype "passive"))
      (node (ref "U1") (pin "33") (pinfunction "PAD_33") (pintype "passive"))
    )
    (net (code "27") (name "Net-(C1-Pad2)") (class "Default")
      (node (ref "C1") (pin "2") (pinfunction "2_2") (pintype "passive"))
      (node (ref "R3") (pin "2") (pinfunction "2_2") (pintype "passive"))
      (node (ref "R4") (pin "1") (pinfunction "1_1") (pintype "passive"))
    )
    (net (code "28") (name "Net-(C2-Pad1)") (class "Default")
      (node (ref "C2") (pin "1") (pinfunction "1_1") (pintype "passive"))
      (node (ref "R1") (pin "1") (pinfunction "1_1") (pintype "passive"))
    )
    (net (code "29") (name "Net-(C7-Pad1)") (class "Default")
      (node (ref "C7") (pin "1") (pinfunction "1_1") (pintype "passive"))
      (node (ref "R5") (pin "2") (pinfunction "2_2") (pintype "passive"))
    )
    (net (code "30") (name "Net-(C13-Pad2)") (class "Default")
      (node (ref "C13") (pin "2") (pinfunction "2_2") (pintype "passive"))
      (node (ref "R7") (pin "2") (pinfunction "2_2") (pintype "passive"))
      (node (ref "R9") (pin "1") (pinfunction "1_1") (pintype "passive"))
    )
    (net (code "31") (name "Net-(C14-Pad1)") (class "Default")
      (node (ref "C14") (pin "1") (pinfunction "1_1") (pintype "passive"))
      (node (ref "R8") (pin "1") (pinfunction "1_1") (pintype "passive"))
    )
    (net (code "32") (name "Net-(C15-Pad1)") (class "Default")
      (node (ref "C15") (pin "1") (pinfunction "1_1") (pintype "passive"))
      (node (ref "R10") (pin "2") (pinfunction "2_2") (pintype "passive"))
    )
    (net (code "33") (name "Net-(C20-Pad2)") (class "Default")
      (node (ref "C20") (pin "2") (pinfunction "2_2") (pintype "passive"))
      (node (ref "R14") (pin "2") (pinfunction "2_2") (pintype "passive"))
      (node (ref "R16") (pin "1") (pinfunction "1_1") (pintype "passive"))
    )
    (net (code "34") (name "Net-(C24-Pad1)") (class "Default")
      (node (ref "C24") (pin "1") (pinfunction "1_1") (pintype "passive"))
      (node (ref "R15") (pin "1") (pinfunction "1_1") (pintype "passive"))
    )
    (net (code "35") (name "Net-(C25-Pad1)") (class "Default")
      (node (ref "C25") (pin "1") (pinfunction "1_1") (pintype "passive"))
      (node (ref "R17") (pin "2") (pinfunction "2_2") (pintype "passive"))
    )
    (net (code "36") (name "Net-(J5-Pad1)") (class "Default")
      (node (ref "J5") (pin "1") (pinfunction "1_1") (pintype "passive"))
      (node (ref "R18") (pin "1") (pinfunction "1_1") (pintype "passive"))
      (node (ref "R22") (pin "2") (pinfunction "2_2") (pintype "passive"))
    )
    (net (code "37") (name "Net-(J6-Pad1)") (class "Default")
      (node (ref "J6") (pin "1") (pinfunction "1_1") (pintype "passive"))
      (node (ref "R19") (pin "1") (pinfunction "1_1") (pintype "passive"))
      (node (ref "R23") (pin "2") (pinfunction "2_2") (pintype "passive"))
    )
    (net (code "38") (name "Net-(J7-Pad1)") (class "Default")
      (node (ref "J7") (pin "1") (pinfunction "1_1") (pintype "passive"))
      (node (ref "R20") (pin "1") (pinfunction "1_1") (pintype "passive"))
      (node (ref "R24") (pin "2") (pinfunction "2_2") (pintype "passive"))
    )
    (net (code "39") (name "Net-(J8-Pad1)") (class "Default")
      (node (ref "J8") (pin "1") (pinfunction "1_1") (pintype "passive"))
      (node (ref "R21") (pin "1") (pinfunction "1_1") (pintype "passive"))
    )
    (net (code "40") (name "unconnected-(U1-PGOOD-Pad2)") (class "Default")
      (node (ref "U1") (pin "2") (pinfunction "PGOOD_2") (pintype "input+no_connect"))
    )
  )
)
